# ThermoPi_A.net
KiCad netlist of a schematic drawn in EAGLE
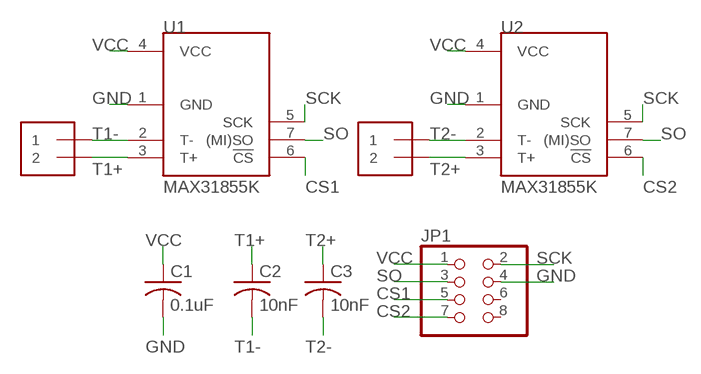
[diagram p0: schematic, sheet 1]

(export (version "E")
  (design (tool "Eeschema 10.0.6"))
  (components
    (comp (ref "C1")
      (value "0.1uF")
      (footprint "eagle-import:C0603")
      (libsource (lib "eagle-import") (part "C-USC0603"))
    )
    (comp (ref "C2")
      (value "10nF")
      (footprint "eagle-import:C0603")
      (libsource (lib "eagle-import") (part "C-USC0603"))
    )
    (comp (ref "C3")
      (value "10nF")
      (footprint "eagle-import:C0603")
      (libsource (lib "eagle-import") (part "C-USC0603"))
    )
    (comp (ref "J1")
      (value "1X2-3.5MM")
      (footprint "eagle-import:1X2-3.5MM")
      (libsource (lib "eagle-import") (part "1X2-3.5MM"))
    )
    (comp (ref "J2")
      (value "1X2-3.5MM")
      (footprint "eagle-import:1X2-3.5MM")
      (libsource (lib "eagle-import") (part "1X2-3.5MM"))
    )
    (comp (ref "JP1")
      (value "PINHD-2X4")
      (footprint "eagle-import:2X04")
      (libsource (lib "eagle-import") (part "PINHD-2X4"))
    )
    (comp (ref "U1")
      (value "MAX31855K")
      (footprint "eagle-import:SO08")
      (libsource (lib "eagle-import") (part "MAX31855K"))
    )
    (comp (ref "U2")
      (value "MAX31855K")
      (footprint "eagle-import:SO08")
      (libsource (lib "eagle-import") (part "MAX31855K"))
    )
  )
  (nets
    (net (code "1") (name "/CS1") (class "Default")
      (node (ref "JP1") (pin "5") (pinfunction "5_5") (pintype "passive"))
      (node (ref "U1") (pin "6") (pinfunction "~{CS}_6") (pintype "bidirectional"))
    )
    (net (code "2") (name "/CS2") (class "Default")
      (node (ref "JP1") (pin "7") (pinfunction "7_7") (pintype "passive"))
      (node (ref "U2") (pin "6") (pinfunction "~{CS}_6") (pintype "bidirectional"))
    )
    (net (code "3") (name "/GND") (class "Default")
      (node (ref "C1") (pin "2") (pinfunction "2_2") (pintype "passive"))
      (node (ref "JP1") (pin "4") (pinfunction "4_4") (pintype "passive"))
      (node (ref "U1") (pin "1") (pinfunction "GND_1") (pintype "bidirectional"))
      (node (ref "U2") (pin "1") (pinfunction "GND_1") (pintype "bidirectional"))
    )
    (net (code "4") (name "/SCK") (class "Default")
      (node (ref "JP1") (pin "2") (pinfunction "2_2") (pintype "passive"))
      (node (ref "U1") (pin "5") (pinfunction "SCK_5") (pintype "bidirectional"))
      (node (ref "U2") (pin "5") (pinfunction "SCK_5") (pintype "bidirectional"))
    )
    (net (code "5") (name "/SO") (class "Default")
      (node (ref "JP1") (pin "3") (pinfunction "3_3") (pintype "passive"))
      (node (ref "U1") (pin "7") (pinfunction "(MI)SO_7") (pintype "bidirectional"))
      (node (ref "U2") (pin "7") (pinfunction "(MI)SO_7") (pintype "bidirectional"))
    )
    (net (code "6") (name "/T1+") (class "Default")
      (node (ref "C2") (pin "1") (pinfunction "1_1") (pintype "passive"))
      (node (ref "J1") (pin "2") (pinfunction "2_2") (pintype "passive"))
      (node (ref "U1") (pin "3") (pinfunction "T+_3") (pintype "bidirectional"))
    )
    (net (code "7") (name "/T1-") (class "Default")
      (node (ref "C2") (pin "2") (pinfunction "2_2") (pintype "passive"))
      (node (ref "J1") (pin "1") (pinfunction "1_1") (pintype "passive"))
      (node (ref "U1") (pin "2") (pinfunction "T-_2") (pintype "bidirectional"))
    )
    (net (code "8") (name "/T2+") (class "Default")
      (node (ref "C3") (pin "1") (pinfunction "1_1") (pintype "passive"))
      (node (ref "J2") (pin "2") (pinfunction "2_2") (pintype "passive"))
      (node (ref "U2") (pin "3") (pinfunction "T+_3") (pintype "bidirectional"))
    )
    (net (code "9") (name "/T2-") (class "Default")
      (node (ref "C3") (pin "2") (pinfunction "2_2") (pintype "passive"))
      (node (ref "J2") (pin "1") (pinfunction "1_1") (pintype "passive"))
      (node (ref "U2") (pin "2") (pinfunction "T-_2") (pintype "bidirectional"))
    )
    (net (code "10") (name "/VCC") (class "Default")
      (node (ref "C1") (pin "1") (pinfunction "1_1") (pintype "passive"))
      (node (ref "JP1") (pin "1") (pinfunction "1_1") (pintype "passive"))
      (node (ref "U1") (pin "4") (pinfunction "VCC_4") (pintype "bidirectional"))
      (node (ref "U2") (pin "4") (pinfunction "VCC_4") (pintype "bidirectional"))
    )
    (net (code "11") (name "unconnected-(JP1-Pad6)") (class "Default")
      (node (ref "JP1") (pin "6") (pinfunction "6_6") (pintype "passive"))
    )
    (net (code "12") (name "unconnected-(JP1-Pad8)") (class "Default")
      (node (ref "JP1") (pin "8") (pinfunction "8_8") (pintype "passive"))
    )
  )
)
